# 1_Schematic_Antenna_Mini-Whip_TH.net
KiCad netlist of a schematic drawn in EasyEDA
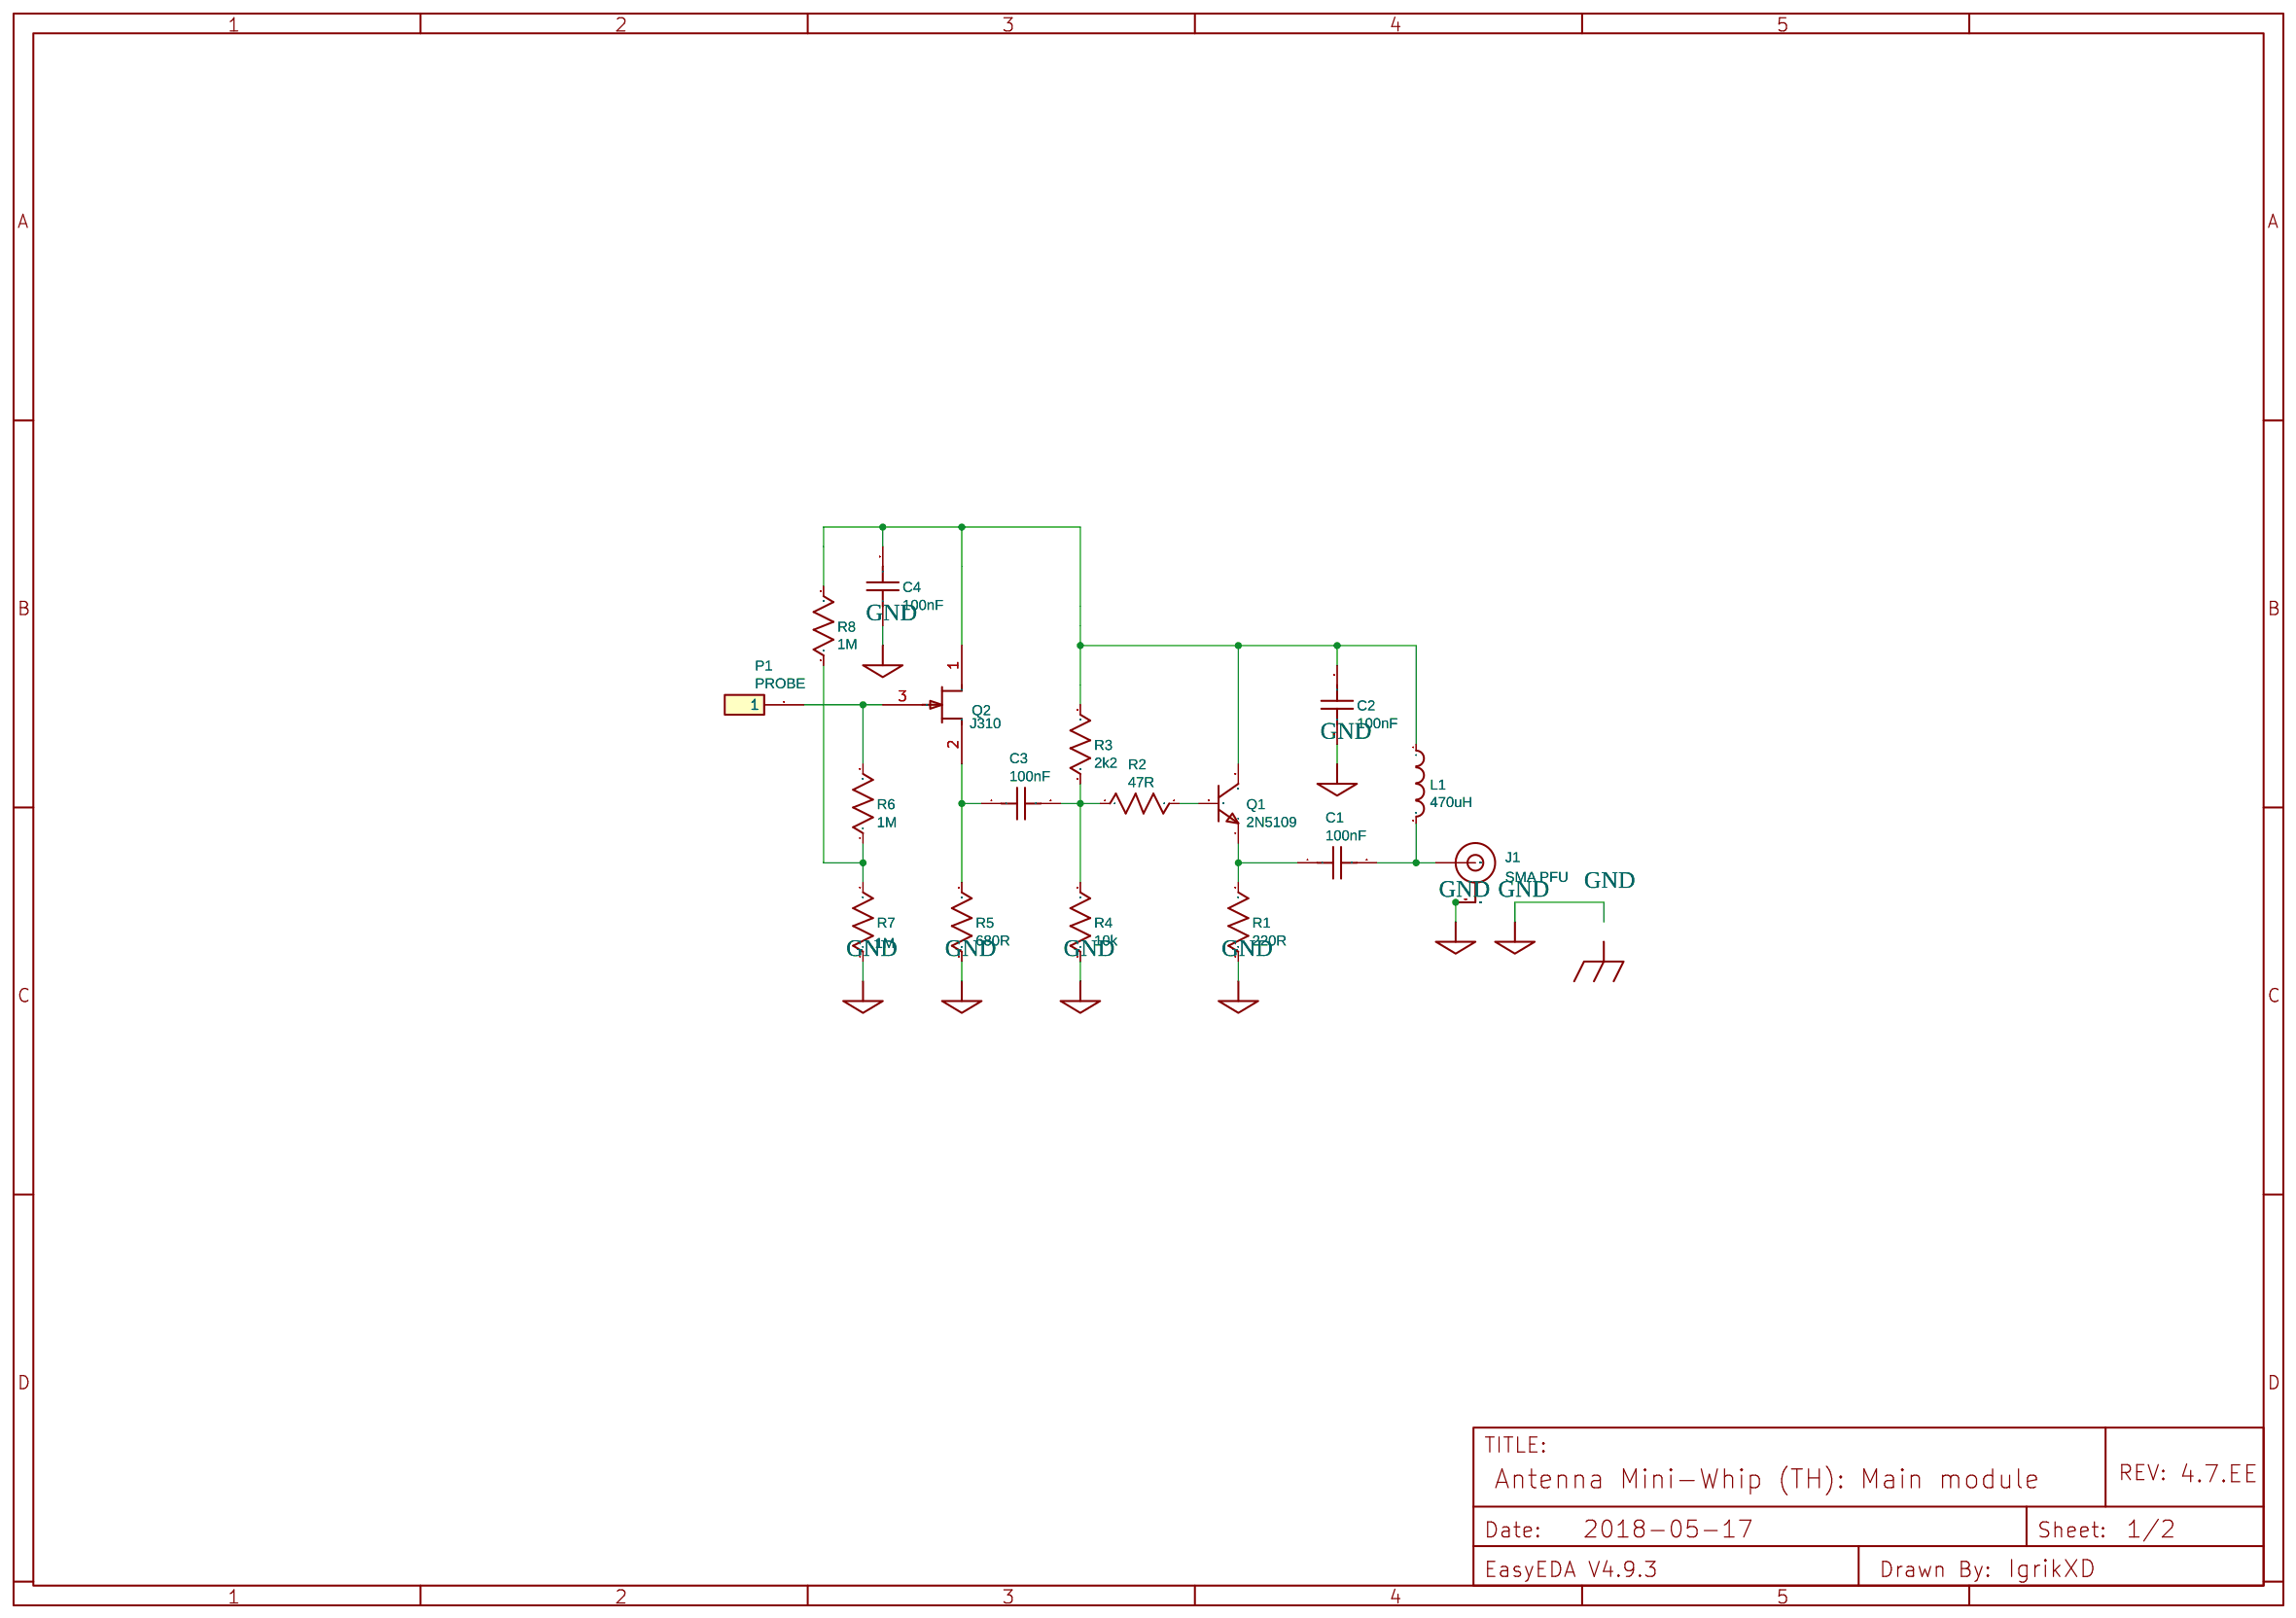
[diagram p0: Antenna Mini-Whip (TH): Main module]
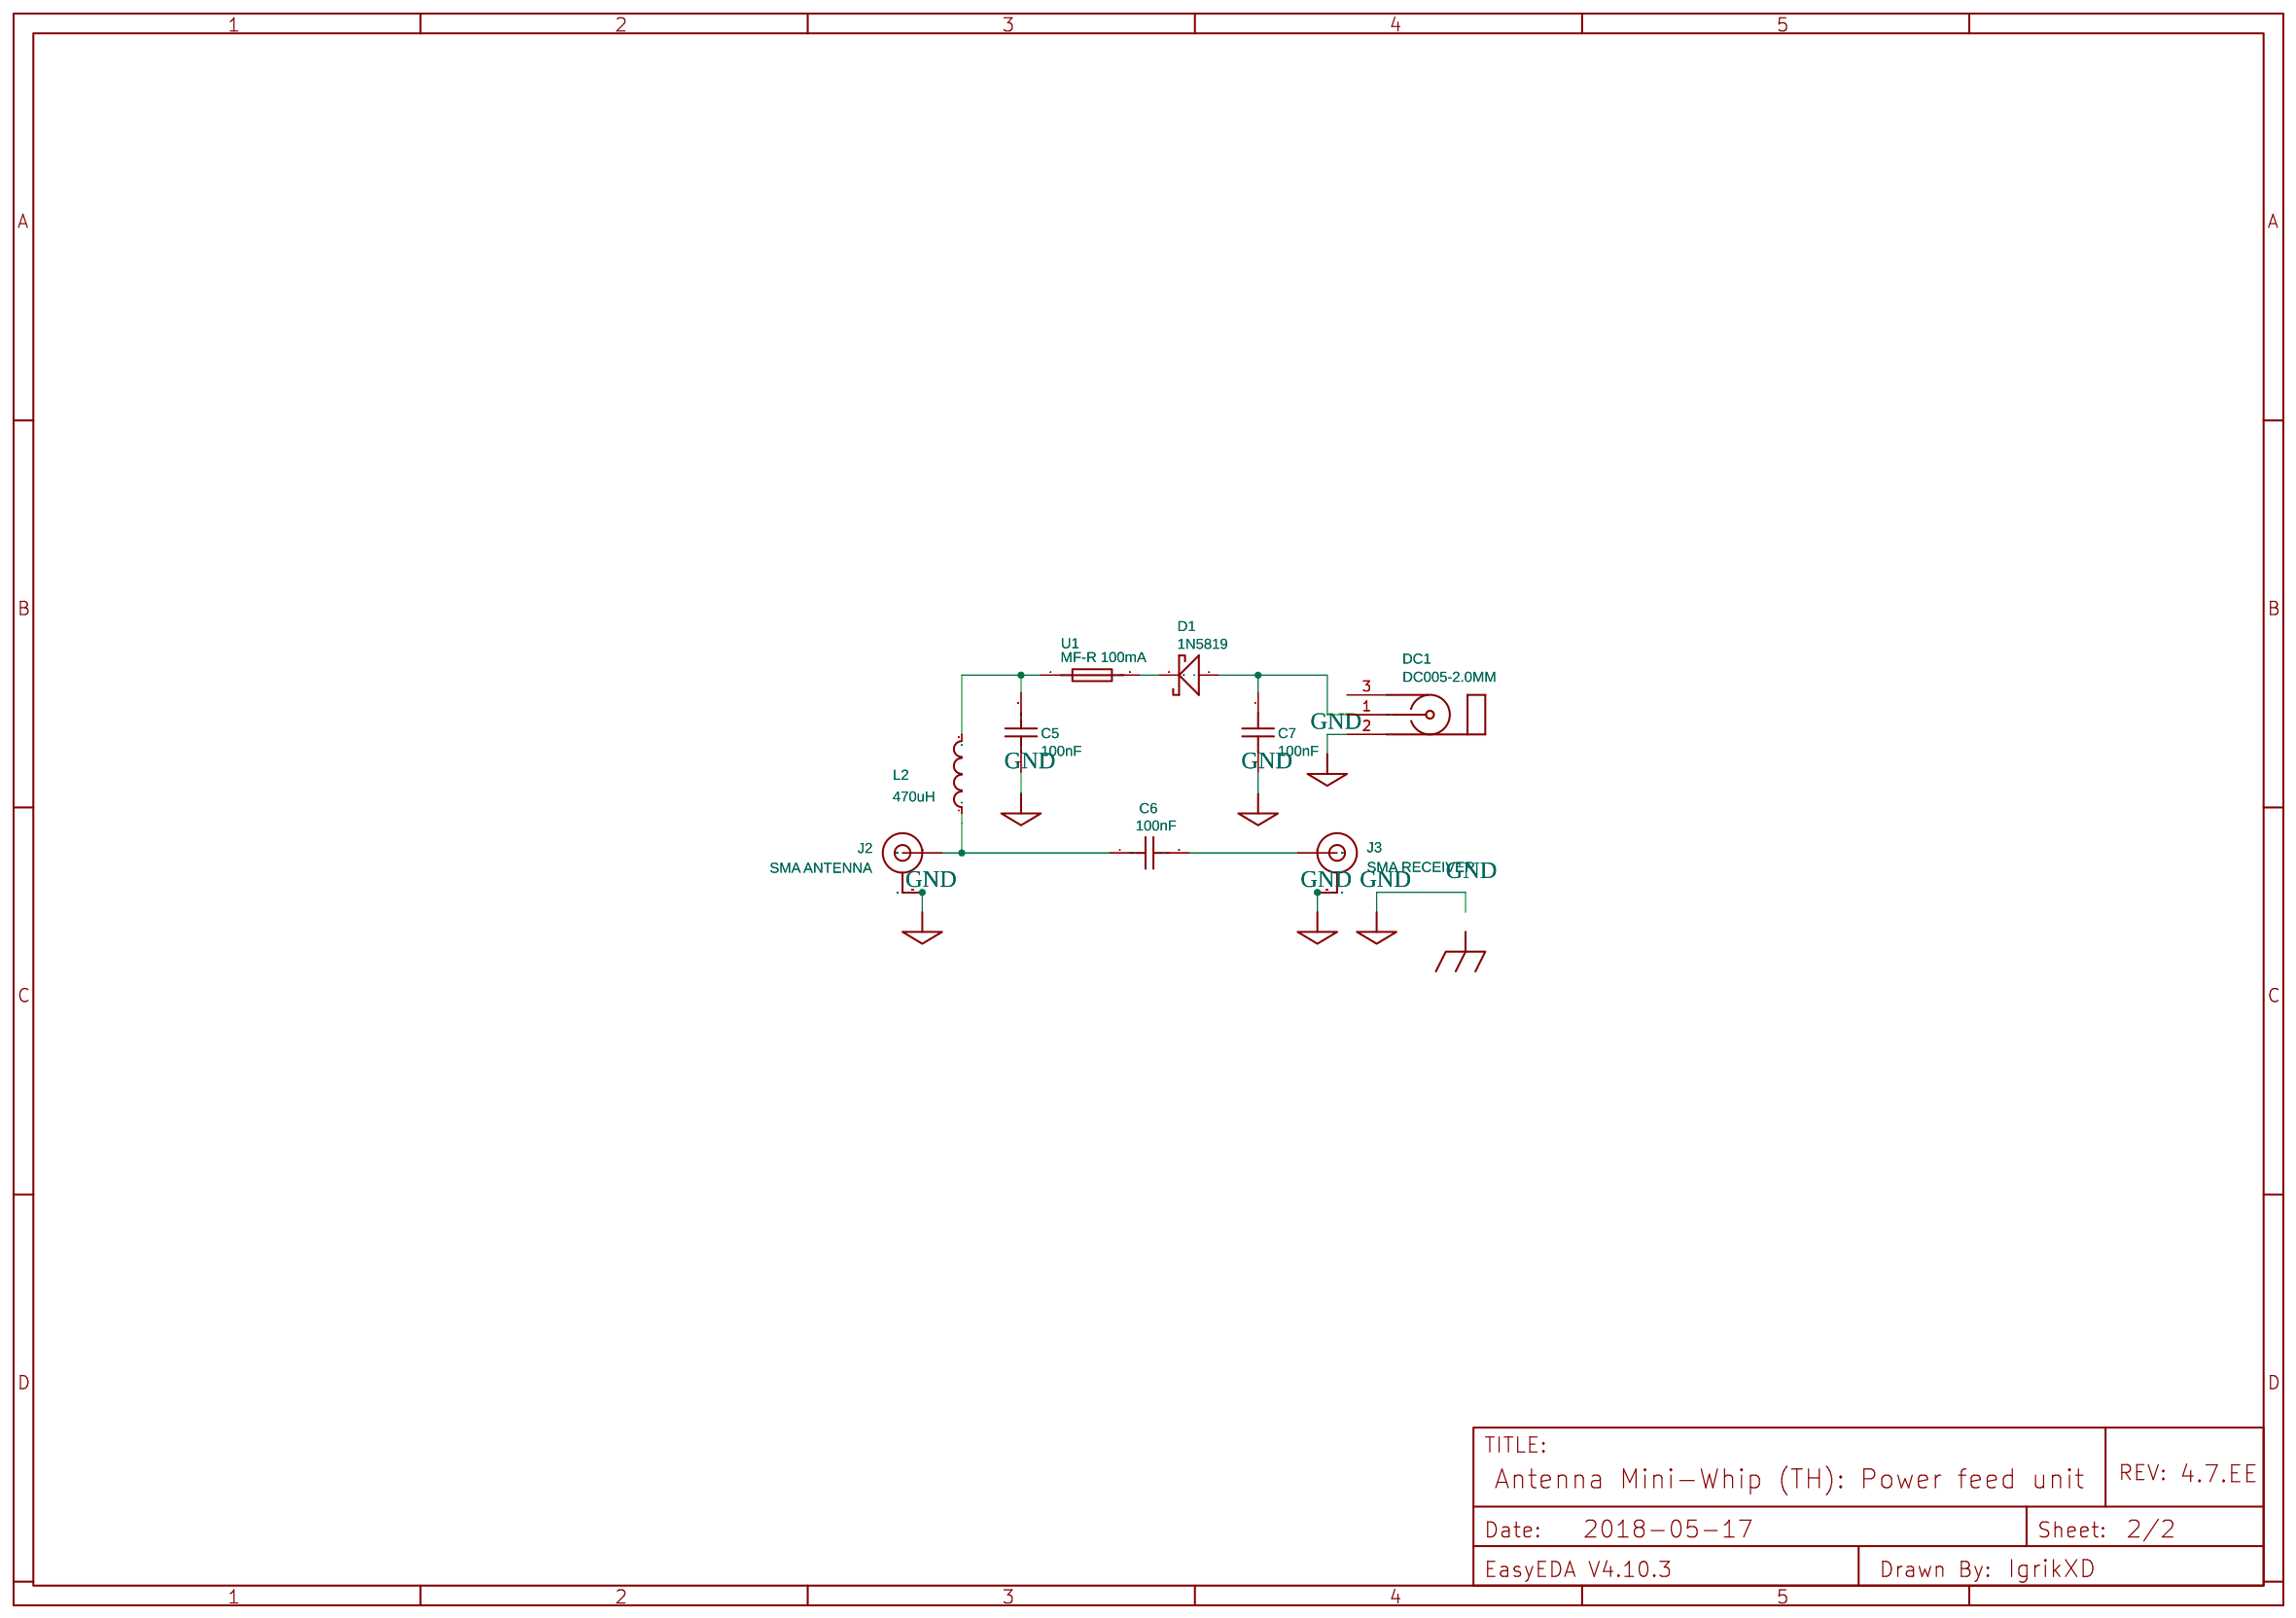
[diagram p1: Antenna Mini-Whip (TH): Power feed unit]

(export (version "E")
  (design (tool "Eeschema 10.0.6"))
  (components
    (comp (ref "C1")
      (value "100nF")
      (fields (field (name "BOM_Manufacturer Part") "Monolithic0805B104J500F3"))
      (libsource (lib "") (part "Capacitor_1"))
    )
    (comp (ref "C2")
      (value "100nF")
      (fields (field (name "BOM_Manufacturer Part") "Monolithic0805B104J500F3"))
      (libsource (lib "") (part "Capacitor"))
    )
    (comp (ref "C3")
      (value "100nF")
      (fields (field (name "BOM_Manufacturer Part") "Monolithic0805B104J500F3"))
      (libsource (lib "") (part "Capacitor_1"))
    )
    (comp (ref "C4")
      (value "100nF")
      (fields (field (name "BOM_Manufacturer Part") "Monolithic0805B104J500F3"))
      (libsource (lib "") (part "Capacitor"))
    )
    (comp (ref "J1")
      (value "SMA PFU")
      (fields (field (name "BOM_Manufacturer Part") "CON-SMA-EDGE-S"))
      (libsource (lib "") (part "Unknown_740_430"))
    )
    (comp (ref "L1")
      (value "470uH")
      (fields (field (name "BOM_Manufacturer Part") "LGA0510-471KP52E"))
      (libsource (lib "") (part "Inductor"))
    )
    (comp (ref "P1")
      (value "PROBE")
      (fields (field (name "BOM_Manufacturer Part") "Header-Male-2.54_1x1"))
      (libsource (lib "") (part "Unknown_385_350"))
    )
    (comp (ref "Q1") (value "2N5109") (libsource (lib "") (part "Unknown_610_400")))
    (comp (ref "Q2") (value "J310") (libsource (lib "") (part "Unknown_470_350")))
    (comp (ref "R1")
      (value "220R")
      (fields (field (name "BOM_Manufacturer Part") "MFR0W4F2200A50"))
      (libsource (lib "") (part "Resistor"))
    )
    (comp (ref "R2")
      (value "47R")
      (fields (field (name "BOM_Manufacturer Part") "MF1/4W-47Ω±1% T52"))
      (libsource (lib "") (part "Resistor_1"))
    )
    (comp (ref "R3")
      (value "2k2")
      (fields (field (name "BOM_Manufacturer Part") "MFR0W4F2201A50"))
      (libsource (lib "") (part "Resistor"))
    )
    (comp (ref "R4")
      (value "10k")
      (fields (field (name "BOM_Manufacturer Part") "MFR0W4F1002A50"))
      (libsource (lib "") (part "Resistor"))
    )
    (comp (ref "R5")
      (value "680R")
      (fields (field (name "BOM_Manufacturer Part") "MFR0W4F6800A50"))
      (libsource (lib "") (part "Resistor"))
    )
    (comp (ref "R6")
      (value "1M")
      (fields (field (name "BOM_Manufacturer Part") "MFR0W4F1004A50"))
      (libsource (lib "") (part "Resistor"))
    )
    (comp (ref "R7")
      (value "1M")
      (fields (field (name "BOM_Manufacturer Part") "MFR0W4F1004A50"))
      (libsource (lib "") (part "Resistor"))
    )
    (comp (ref "R8")
      (value "1M")
      (fields (field (name "BOM_Manufacturer Part") "MFR0W4F1004A50"))
      (libsource (lib "") (part "Resistor"))
    )
    (comp (ref "C5")
      (value "100nF")
      (fields (field (name "BOM_Manufacturer Part") "Monolithic0805B104J500F3"))
      (libsource (lib "") (part "Capacitor_1"))
    )
    (comp (ref "C6")
      (value "100nF")
      (fields (field (name "BOM_Manufacturer Part") "Monolithic0805B104J500F3"))
      (libsource (lib "") (part "Capacitor"))
    )
    (comp (ref "C7")
      (value "100nF")
      (fields (field (name "BOM_Manufacturer Part") "Monolithic0805B104J500F3"))
      (libsource (lib "") (part "Capacitor_1"))
    )
    (comp (ref "D1")
      (value "1N5819")
      (fields (field (name "BOM_Manufacturer Part") "?"))
      (libsource (lib "") (part "Unknown_595_335"))
    )
    (comp (ref "DC1")
      (value "DC005-2.0MM")
      (fields (field (name "BOM_Manufacturer Part") "DC-005 5.5-2.0MM"))
      (libsource (lib "") (part "Unknown_705_355"))
    )
    (comp (ref "J2")
      (value "SMA ANTENNA")
      (fields (field (name "BOM_Manufacturer Part") "CON-SMA-EDGE-S"))
      (libsource (lib "") (part "Unknown_450_425"))
    )
    (comp (ref "J3")
      (value "SMA RECEIVER")
      (fields (field (name "BOM_Manufacturer Part") "CON-SMA-EDGE-S"))
      (libsource (lib "") (part "Unknown_670_425"))
    )
    (comp (ref "L2")
      (value "470uH")
      (fields (field (name "BOM_Manufacturer Part") "LGA0510-471KP52E"))
      (libsource (lib "") (part "Inductor"))
    )
    (comp (ref "U1")
      (value "MF-R 100mA")
      (fields (field (name "BOM_Manufacturer Part") "MF-R010"))
      (libsource (lib "") (part "Unknown_540_335"))
    )
  )
  (nets
    (net (code "1") (name "GND") (class "Default")
      (node (ref "C2") (pin "1") (pinfunction "1_1") (pintype "unspecified"))
      (node (ref "C4") (pin "1") (pinfunction "1_1") (pintype "unspecified"))
      (node (ref "C5") (pin "1") (pinfunction "1_1") (pintype "unspecified"))
      (node (ref "C7") (pin "1") (pinfunction "1_1") (pintype "unspecified"))
      (node (ref "DC1") (pin "2") (pinfunction "2_2") (pintype "input"))
      (node (ref "J1") (pin "GND@0") (pinfunction "GND_GND@0") (pintype "unspecified"))
      (node (ref "J1") (pin "GND@1") (pinfunction "GND_GND@1") (pintype "unspecified"))
      (node (ref "J1") (pin "GND@2") (pinfunction "GND_GND@2") (pintype "unspecified"))
      (node (ref "J1") (pin "GND@3") (pinfunction "GND_GND@3") (pintype "unspecified"))
      (node (ref "J2") (pin "GND@0") (pinfunction "GND_GND@0") (pintype "unspecified"))
      (node (ref "J2") (pin "GND@1") (pinfunction "GND_GND@1") (pintype "unspecified"))
      (node (ref "J2") (pin "GND@2") (pinfunction "GND_GND@2") (pintype "unspecified"))
      (node (ref "J2") (pin "GND@3") (pinfunction "GND_GND@3") (pintype "unspecified"))
      (node (ref "J3") (pin "GND@0") (pinfunction "GND_GND@0") (pintype "unspecified"))
      (node (ref "J3") (pin "GND@1") (pinfunction "GND_GND@1") (pintype "unspecified"))
      (node (ref "J3") (pin "GND@2") (pinfunction "GND_GND@2") (pintype "unspecified"))
      (node (ref "J3") (pin "GND@3") (pinfunction "GND_GND@3") (pintype "unspecified"))
      (node (ref "R1") (pin "1") (pinfunction "1_1") (pintype "unspecified"))
      (node (ref "R4") (pin "1") (pinfunction "1_1") (pintype "unspecified"))
      (node (ref "R5") (pin "1") (pinfunction "1_1") (pintype "unspecified"))
      (node (ref "R7") (pin "1") (pinfunction "1_1") (pintype "unspecified"))
    )
    (net (code "2") (name "Net-(C3-Pad2)") (class "Default")
      (node (ref "C3") (pin "2") (pinfunction "2_2") (pintype "unspecified"))
      (node (ref "R2") (pin "1") (pinfunction "1_1") (pintype "unspecified"))
      (node (ref "R3") (pin "1") (pinfunction "1_1") (pintype "unspecified"))
      (node (ref "R4") (pin "2") (pinfunction "2_2") (pintype "unspecified"))
    )
    (net (code "3") (name "Net-(C5-Pad2)") (class "Default")
      (node (ref "C5") (pin "2") (pinfunction "2_2") (pintype "unspecified"))
      (node (ref "L2") (pin "2") (pinfunction "2_2") (pintype "unspecified"))
      (node (ref "U1") (pin "1") (pinfunction "1_1") (pintype "unspecified"))
    )
    (net (code "4") (name "Net-(D1-PadC)") (class "Default")
      (node (ref "D1") (pin "C") (pinfunction "C_C") (pintype "unspecified"))
      (node (ref "U1") (pin "2") (pinfunction "2_2") (pintype "unspecified"))
    )
    (net (code "5") (name "Net-(DC1-VCC)") (class "Default")
      (node (ref "C7") (pin "2") (pinfunction "2_2") (pintype "unspecified"))
      (node (ref "D1") (pin "A") (pinfunction "A_A") (pintype "unspecified"))
      (node (ref "DC1") (pin "1") (pinfunction "VCC_1") (pintype "input"))
    )
    (net (code "6") (name "Net-(J1-SIGNAL)") (class "Default")
      (node (ref "C1") (pin "2") (pinfunction "2_2") (pintype "unspecified"))
      (node (ref "J1") (pin "SIG") (pinfunction "SIGNAL_SIG") (pintype "unspecified"))
      (node (ref "L1") (pin "2") (pinfunction "2_2") (pintype "unspecified"))
    )
    (net (code "7") (name "Net-(J2-SIGNAL)") (class "Default")
      (node (ref "C6") (pin "1") (pinfunction "1_1") (pintype "unspecified"))
      (node (ref "J2") (pin "SIG") (pinfunction "SIGNAL_SIG") (pintype "unspecified"))
      (node (ref "L2") (pin "1") (pinfunction "1_1") (pintype "unspecified"))
    )
    (net (code "8") (name "Net-(J3-SIGNAL)") (class "Default")
      (node (ref "C6") (pin "2") (pinfunction "2_2") (pintype "unspecified"))
      (node (ref "J3") (pin "SIG") (pinfunction "SIGNAL_SIG") (pintype "unspecified"))
    )
    (net (code "9") (name "Net-(Q1-B)") (class "Default")
      (node (ref "Q1") (pin "2") (pinfunction "B_2") (pintype "unspecified"))
      (node (ref "R2") (pin "2") (pinfunction "2_2") (pintype "unspecified"))
    )
    (net (code "10") (name "Net-(Q1-C)") (class "Default")
      (node (ref "C2") (pin "2") (pinfunction "2_2") (pintype "unspecified"))
      (node (ref "C4") (pin "2") (pinfunction "2_2") (pintype "unspecified"))
      (node (ref "L1") (pin "1") (pinfunction "1_1") (pintype "unspecified"))
      (node (ref "Q1") (pin "3") (pinfunction "C_3") (pintype "unspecified"))
      (node (ref "Q2") (pin "1") (pinfunction "D_1") (pintype "unspecified"))
      (node (ref "R3") (pin "2") (pinfunction "2_2") (pintype "unspecified"))
      (node (ref "R8") (pin "2") (pinfunction "2_2") (pintype "unspecified"))
    )
    (net (code "11") (name "Net-(Q1-E)") (class "Default")
      (node (ref "C1") (pin "1") (pinfunction "1_1") (pintype "unspecified"))
      (node (ref "Q1") (pin "1") (pinfunction "E_1") (pintype "unspecified"))
      (node (ref "R1") (pin "2") (pinfunction "2_2") (pintype "unspecified"))
    )
    (net (code "12") (name "Net-(Q2-G)") (class "Default")
      (node (ref "P1") (pin "1") (pinfunction "1_1") (pintype "input"))
      (node (ref "Q2") (pin "3") (pinfunction "G_3") (pintype "unspecified"))
      (node (ref "R6") (pin "2") (pinfunction "2_2") (pintype "unspecified"))
    )
    (net (code "13") (name "Net-(Q2-S)") (class "Default")
      (node (ref "C3") (pin "1") (pinfunction "1_1") (pintype "unspecified"))
      (node (ref "Q2") (pin "2") (pinfunction "S_2") (pintype "unspecified"))
      (node (ref "R5") (pin "2") (pinfunction "2_2") (pintype "unspecified"))
    )
    (net (code "14") (name "Net-(R6-Pad1)") (class "Default")
      (node (ref "R6") (pin "1") (pinfunction "1_1") (pintype "unspecified"))
      (node (ref "R7") (pin "2") (pinfunction "2_2") (pintype "unspecified"))
      (node (ref "R8") (pin "1") (pinfunction "1_1") (pintype "unspecified"))
    )
    (net (code "15") (name "unconnected-(DC1-Pad3)") (class "Default")
      (node (ref "DC1") (pin "3") (pinfunction "3_3") (pintype "input"))
    )
  )
)
